# COMS0007_ModemRXMux.net
KiCad netlist of a schematic drawn in Altium Designer
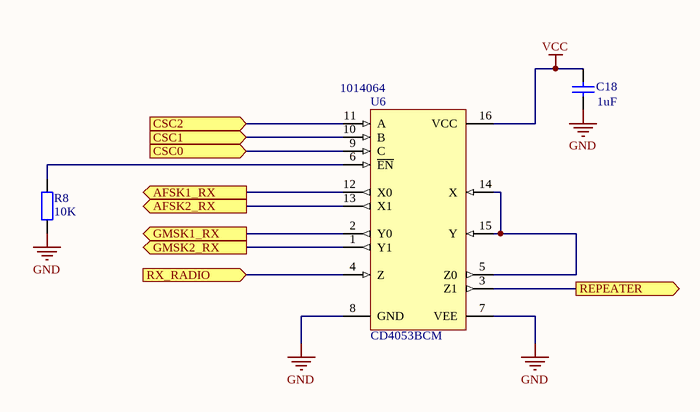
[diagram p0: COMS0007 ModemRXMux.SchDoc]

(export (version "E")
  (design (tool "Eeschema 10.0.6"))
  (components
    (comp (ref "C18")
      (value "1uF")
      (footprint "0805")
      (description "Capacitor")
      (fields (field (name "Comment") "C1210") (field (name "PUBLISHER") "Altium Limited"))
      (libsource (lib "Miscellaneous Devices") (part "Cap"))
    )
    (comp (ref "R8")
      (value "10K")
      (footprint "RESC2012N")
      (description "Resistor")
      (fields (field (name "Comment") "Res1") (field (name "PUBLISHER") "Altium Limited"))
      (libsource (lib "Miscellaneous Devices") (part "Res2"))
    )
    (comp (ref "U6")
      (value "CD4053BCM")
      (footprint "M16A_M")
      (description "Triple 2-Channnel Analog Multiplexer/Demutiplexer")
      (fields (field (name "SUPPLIER PART NUMBER 1") "1014064") (field (name "PUBLISHER") "Altium Limited"))
      (libsource (lib "FSC Logic Multiplexer") (part "CD4053BCM"))
    )
  )
  (nets
    (net (code "1") (name "/AFSK1_RX") (class "Default")
      (node (ref "U6") (pin "12") (pinfunction "X0_12") (pintype "output"))
    )
    (net (code "2") (name "/AFSK2_RX") (class "Default")
      (node (ref "U6") (pin "13") (pinfunction "X1_13") (pintype "output"))
    )
    (net (code "3") (name "/CSC0") (class "Default")
      (node (ref "U6") (pin "9") (pinfunction "C_9") (pintype "input"))
    )
    (net (code "4") (name "/CSC1") (class "Default")
      (node (ref "U6") (pin "10") (pinfunction "B_10") (pintype "input"))
    )
    (net (code "5") (name "/CSC2") (class "Default")
      (node (ref "U6") (pin "11") (pinfunction "A_11") (pintype "input"))
    )
    (net (code "6") (name "/GMSK1_RX") (class "Default")
      (node (ref "U6") (pin "2") (pinfunction "Y0_2") (pintype "output"))
    )
    (net (code "7") (name "/GMSK2_RX") (class "Default")
      (node (ref "U6") (pin "1") (pinfunction "Y1_1") (pintype "output"))
    )
    (net (code "8") (name "/REPEATER") (class "Default")
      (node (ref "U6") (pin "3") (pinfunction "Z1_3") (pintype "output"))
    )
    (net (code "9") (name "/RX_RADIO") (class "Default")
      (node (ref "U6") (pin "4") (pinfunction "Z_4") (pintype "input"))
    )
    (net (code "10") (name "GND") (class "Default")
      (node (ref "C18") (pin "1") (pinfunction "1_1") (pintype "passive"))
      (node (ref "R8") (pin "1") (pinfunction "1_1") (pintype "passive"))
      (node (ref "U6") (pin "7") (pinfunction "VEE_7") (pintype "power_in"))
      (node (ref "U6") (pin "8") (pinfunction "GND_8") (pintype "power_in"))
    )
    (net (code "11") (name "Net-(U6-X)") (class "Default")
      (node (ref "U6") (pin "14") (pinfunction "X_14") (pintype "input"))
      (node (ref "U6") (pin "15") (pinfunction "Y_15") (pintype "input"))
      (node (ref "U6") (pin "5") (pinfunction "Z0_5") (pintype "output"))
    )
    (net (code "12") (name "Net-(U6-~{EN})") (class "Default")
      (node (ref "R8") (pin "2") (pinfunction "2_2") (pintype "passive"))
      (node (ref "U6") (pin "6") (pinfunction "~{EN}_6") (pintype "input"))
    )
    (net (code "13") (name "VCC") (class "Default")
      (node (ref "C18") (pin "2") (pinfunction "2_2") (pintype "passive"))
      (node (ref "U6") (pin "16") (pinfunction "VCC_16") (pintype "power_in"))
    )
  )
)
